# AS3364_bus_mixer_v2_1.net
KiCad netlist of a schematic drawn in EAGLE
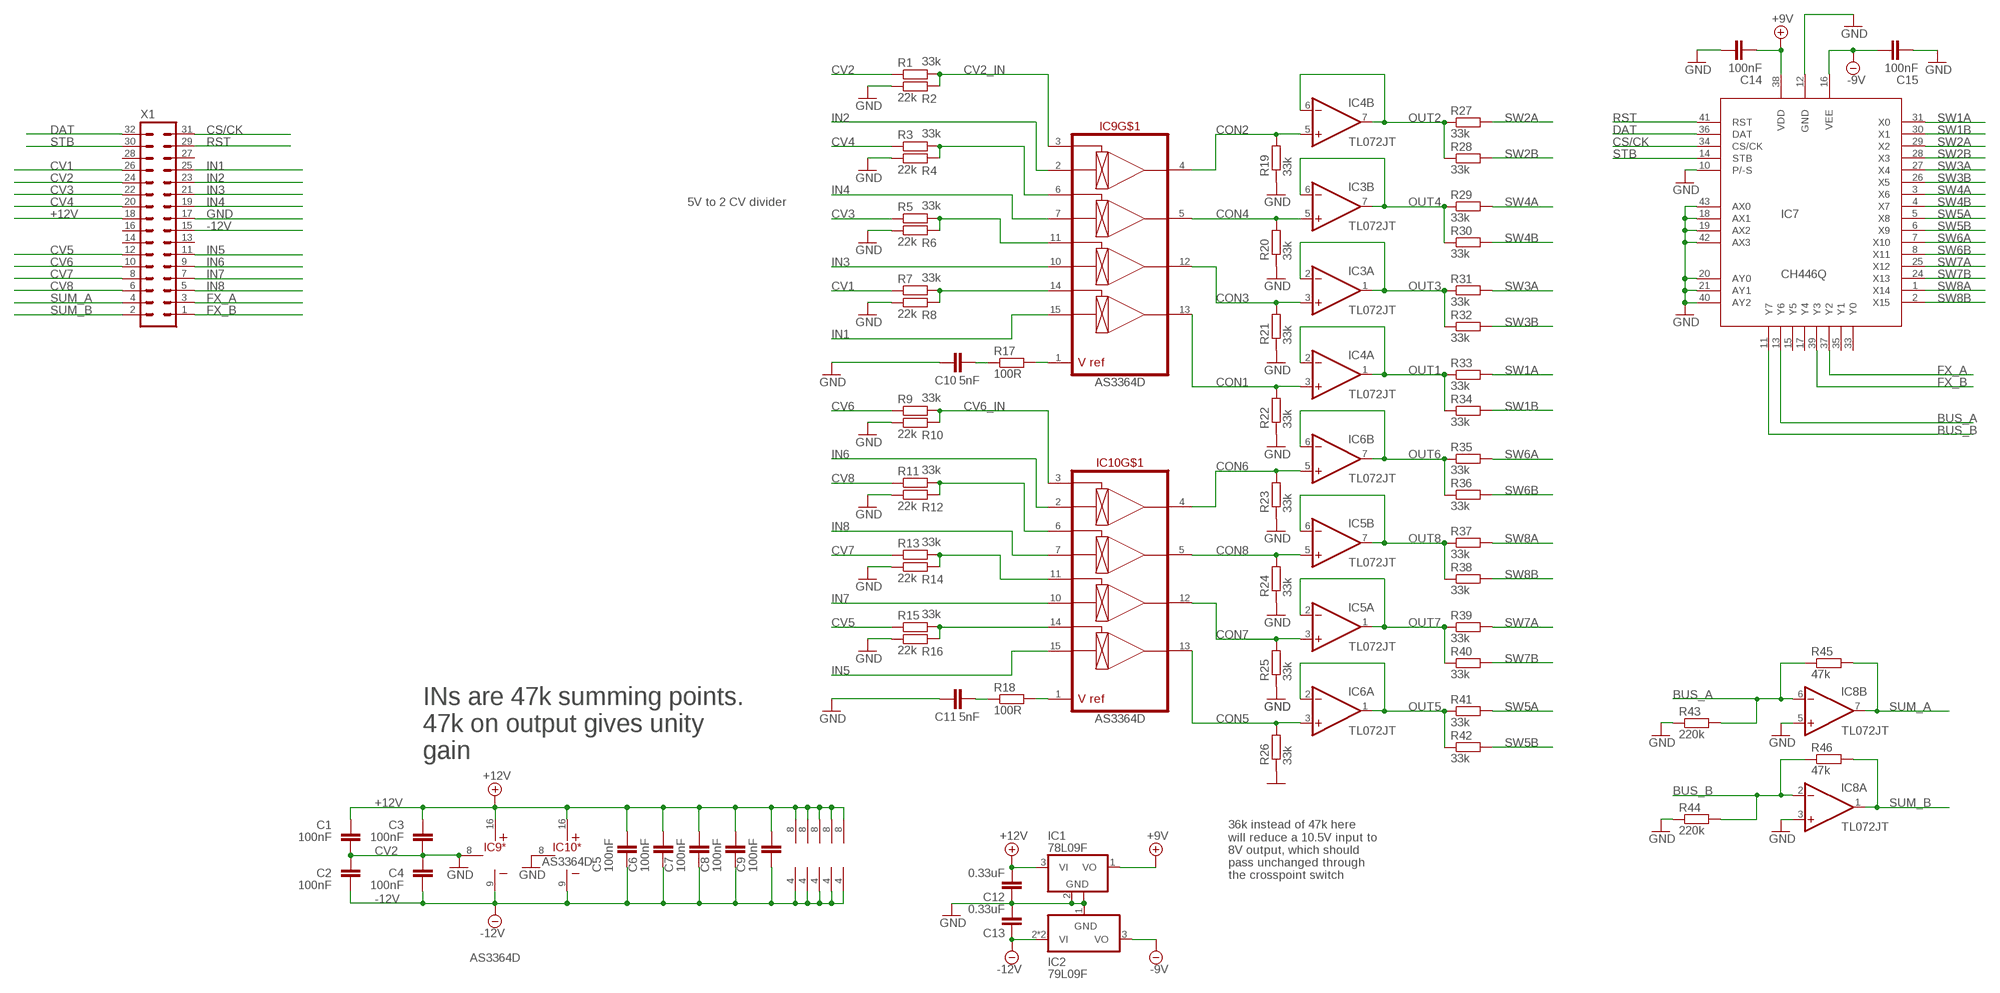
[diagram p0: schematic, sheet 1]

(export (version "E")
  (design (tool "Eeschema 10.0.6"))
  (components
    (comp (ref "C1")
      (value "100nF")
      (footprint "eagle-import:C0402")
      (libsource (lib "eagle-import") (part "C-EUC0402"))
    )
    (comp (ref "C2")
      (value "100nF")
      (footprint "eagle-import:C0402")
      (libsource (lib "eagle-import") (part "C-EUC0402"))
    )
    (comp (ref "C3")
      (value "100nF")
      (footprint "eagle-import:C0402")
      (libsource (lib "eagle-import") (part "C-EUC0402"))
    )
    (comp (ref "C4")
      (value "100nF")
      (footprint "eagle-import:C0402")
      (libsource (lib "eagle-import") (part "C-EUC0402"))
    )
    (comp (ref "C5")
      (value "100nF")
      (footprint "eagle-import:C0402")
      (libsource (lib "eagle-import") (part "C-EUC0402"))
    )
    (comp (ref "C6")
      (value "100nF")
      (footprint "eagle-import:C0402")
      (libsource (lib "eagle-import") (part "C-EUC0402"))
    )
    (comp (ref "C7")
      (value "100nF")
      (footprint "eagle-import:C0402")
      (libsource (lib "eagle-import") (part "C-EUC0402"))
    )
    (comp (ref "C8")
      (value "100nF")
      (footprint "eagle-import:C0402")
      (libsource (lib "eagle-import") (part "C-EUC0402"))
    )
    (comp (ref "C9")
      (value "100nF")
      (footprint "eagle-import:C0402")
      (libsource (lib "eagle-import") (part "C-EUC0402"))
    )
    (comp (ref "C10")
      (value "5nF")
      (footprint "eagle-import:C0402")
      (libsource (lib "eagle-import") (part "C-EUC0402"))
    )
    (comp (ref "C11")
      (value "5nF")
      (footprint "eagle-import:C0402")
      (libsource (lib "eagle-import") (part "C-EUC0402"))
    )
    (comp (ref "C12")
      (value "0.33uF")
      (footprint "eagle-import:C0603")
      (libsource (lib "eagle-import") (part "resistor_C-EUC0603"))
    )
    (comp (ref "C13")
      (value "0.33uF")
      (footprint "eagle-import:C0603")
      (libsource (lib "eagle-import") (part "resistor_C-EUC0603"))
    )
    (comp (ref "C14")
      (value "100nF")
      (footprint "eagle-import:C0402")
      (libsource (lib "eagle-import") (part "C-EUC0402"))
    )
    (comp (ref "C15")
      (value "100nF")
      (footprint "eagle-import:C0402")
      (libsource (lib "eagle-import") (part "C-EUC0402"))
    )
    (comp (ref "IC1")
      (value "78L09F")
      (footprint "eagle-import:SOT89")
      (libsource (lib "eagle-import") (part "78LF09"))
    )
    (comp (ref "IC2")
      (value "79L09F")
      (footprint "eagle-import:SOT89")
      (libsource (lib "eagle-import") (part "79LF09"))
    )
    (comp (ref "IC3")
      (value "TL072JT")
      (footprint "eagle-import:TSSOP8J")
      (libsource (lib "eagle-import") (part "TL072JT"))
    )
    (comp (ref "IC4")
      (value "TL072JT")
      (footprint "eagle-import:TSSOP8J")
      (libsource (lib "eagle-import") (part "TL072JT"))
    )
    (comp (ref "IC5")
      (value "TL072JT")
      (footprint "eagle-import:TSSOP8J")
      (libsource (lib "eagle-import") (part "TL072JT"))
    )
    (comp (ref "IC6")
      (value "TL072JT")
      (footprint "eagle-import:TSSOP8J")
      (libsource (lib "eagle-import") (part "TL072JT"))
    )
    (comp (ref "IC7")
      (value "CH446Q")
      (footprint "eagle-import:LQFP-44-J")
      (libsource (lib "eagle-import") (part "CH446Q"))
    )
    (comp (ref "IC8")
      (value "TL072JT")
      (footprint "eagle-import:TSSOP8J")
      (libsource (lib "eagle-import") (part "TL072JT"))
    )
    (comp (ref "IC9")
      (value "AS3364D")
      (footprint "eagle-import:DIL16J")
      (libsource (lib "eagle-import") (part "AS3364D"))
    )
    (comp (ref "IC10")
      (value "AS3364D")
      (footprint "eagle-import:DIL16J")
      (libsource (lib "eagle-import") (part "AS3364D"))
    )
    (comp (ref "R1")
      (value "33k")
      (footprint "eagle-import:R0402")
      (libsource (lib "eagle-import") (part "R-EU_R0402"))
    )
    (comp (ref "R2")
      (value "22k")
      (footprint "eagle-import:R0402")
      (libsource (lib "eagle-import") (part "R-EU_R0402"))
    )
    (comp (ref "R3")
      (value "33k")
      (footprint "eagle-import:R0402")
      (libsource (lib "eagle-import") (part "R-EU_R0402"))
    )
    (comp (ref "R4")
      (value "22k")
      (footprint "eagle-import:R0402")
      (libsource (lib "eagle-import") (part "R-EU_R0402"))
    )
    (comp (ref "R5")
      (value "33k")
      (footprint "eagle-import:R0402")
      (libsource (lib "eagle-import") (part "R-EU_R0402"))
    )
    (comp (ref "R6")
      (value "22k")
      (footprint "eagle-import:R0402")
      (libsource (lib "eagle-import") (part "R-EU_R0402"))
    )
    (comp (ref "R7")
      (value "33k")
      (footprint "eagle-import:R0402")
      (libsource (lib "eagle-import") (part "R-EU_R0402"))
    )
    (comp (ref "R8")
      (value "22k")
      (footprint "eagle-import:R0402")
      (libsource (lib "eagle-import") (part "R-EU_R0402"))
    )
    (comp (ref "R9")
      (value "33k")
      (footprint "eagle-import:R0402")
      (libsource (lib "eagle-import") (part "R-EU_R0402"))
    )
    (comp (ref "R10")
      (value "22k")
      (footprint "eagle-import:R0402")
      (libsource (lib "eagle-import") (part "R-EU_R0402"))
    )
    (comp (ref "R11")
      (value "33k")
      (footprint "eagle-import:R0402")
      (libsource (lib "eagle-import") (part "R-EU_R0402"))
    )
    (comp (ref "R12")
      (value "22k")
      (footprint "eagle-import:R0402")
      (libsource (lib "eagle-import") (part "R-EU_R0402"))
    )
    (comp (ref "R13")
      (value "33k")
      (footprint "eagle-import:R0402")
      (libsource (lib "eagle-import") (part "R-EU_R0402"))
    )
    (comp (ref "R14")
      (value "22k")
      (footprint "eagle-import:R0402")
      (libsource (lib "eagle-import") (part "R-EU_R0402"))
    )
    (comp (ref "R15")
      (value "33k")
      (footprint "eagle-import:R0402")
      (libsource (lib "eagle-import") (part "R-EU_R0402"))
    )
    (comp (ref "R16")
      (value "22k")
      (footprint "eagle-import:R0402")
      (libsource (lib "eagle-import") (part "R-EU_R0402"))
    )
    (comp (ref "R17")
      (value "100R")
      (footprint "eagle-import:R0402")
      (libsource (lib "eagle-import") (part "R-EU_R0402"))
    )
    (comp (ref "R18")
      (value "100R")
      (footprint "eagle-import:R0402")
      (libsource (lib "eagle-import") (part "R-EU_R0402"))
    )
    (comp (ref "R19")
      (value "33k")
      (footprint "eagle-import:R0402")
      (libsource (lib "eagle-import") (part "R-EU_R0402"))
    )
    (comp (ref "R20")
      (value "33k")
      (footprint "eagle-import:R0402")
      (libsource (lib "eagle-import") (part "R-EU_R0402"))
    )
    (comp (ref "R21")
      (value "33k")
      (footprint "eagle-import:R0402")
      (libsource (lib "eagle-import") (part "R-EU_R0402"))
    )
    (comp (ref "R22")
      (value "33k")
      (footprint "eagle-import:R0402")
      (libsource (lib "eagle-import") (part "R-EU_R0402"))
    )
    (comp (ref "R23")
      (value "33k")
      (footprint "eagle-import:R0402")
      (libsource (lib "eagle-import") (part "R-EU_R0402"))
    )
    (comp (ref "R24")
      (value "33k")
      (footprint "eagle-import:R0402")
      (libsource (lib "eagle-import") (part "R-EU_R0402"))
    )
    (comp (ref "R25")
      (value "33k")
      (footprint "eagle-import:R0402")
      (libsource (lib "eagle-import") (part "R-EU_R0402"))
    )
    (comp (ref "R26")
      (value "33k")
      (footprint "eagle-import:R0402")
      (libsource (lib "eagle-import") (part "R-EU_R0402"))
    )
    (comp (ref "R27")
      (value "33k")
      (footprint "eagle-import:R0402")
      (libsource (lib "eagle-import") (part "R-EU_R0402"))
    )
    (comp (ref "R28")
      (value "33k")
      (footprint "eagle-import:R0402")
      (libsource (lib "eagle-import") (part "R-EU_R0402"))
    )
    (comp (ref "R29")
      (value "33k")
      (footprint "eagle-import:R0402")
      (libsource (lib "eagle-import") (part "R-EU_R0402"))
    )
    (comp (ref "R30")
      (value "33k")
      (footprint "eagle-import:R0402")
      (libsource (lib "eagle-import") (part "R-EU_R0402"))
    )
    (comp (ref "R31")
      (value "33k")
      (footprint "eagle-import:R0402")
      (libsource (lib "eagle-import") (part "R-EU_R0402"))
    )
    (comp (ref "R32")
      (value "33k")
      (footprint "eagle-import:R0402")
      (libsource (lib "eagle-import") (part "R-EU_R0402"))
    )
    (comp (ref "R33")
      (value "33k")
      (footprint "eagle-import:R0402")
      (libsource (lib "eagle-import") (part "R-EU_R0402"))
    )
    (comp (ref "R34")
      (value "33k")
      (footprint "eagle-import:R0402")
      (libsource (lib "eagle-import") (part "R-EU_R0402"))
    )
    (comp (ref "R35")
      (value "33k")
      (footprint "eagle-import:R0402")
      (libsource (lib "eagle-import") (part "R-EU_R0402"))
    )
    (comp (ref "R36")
      (value "33k")
      (footprint "eagle-import:R0402")
      (libsource (lib "eagle-import") (part "R-EU_R0402"))
    )
    (comp (ref "R37")
      (value "33k")
      (footprint "eagle-import:R0402")
      (libsource (lib "eagle-import") (part "R-EU_R0402"))
    )
    (comp (ref "R38")
      (value "33k")
      (footprint "eagle-import:R0402")
      (libsource (lib "eagle-import") (part "R-EU_R0402"))
    )
    (comp (ref "R39")
      (value "33k")
      (footprint "eagle-import:R0402")
      (libsource (lib "eagle-import") (part "R-EU_R0402"))
    )
    (comp (ref "R40")
      (value "33k")
      (footprint "eagle-import:R0402")
      (libsource (lib "eagle-import") (part "R-EU_R0402"))
    )
    (comp (ref "R41")
      (value "33k")
      (footprint "eagle-import:R0402")
      (libsource (lib "eagle-import") (part "R-EU_R0402"))
    )
    (comp (ref "R42")
      (value "33k")
      (footprint "eagle-import:R0402")
      (libsource (lib "eagle-import") (part "R-EU_R0402"))
    )
    (comp (ref "R43")
      (value "220k")
      (footprint "eagle-import:R0402")
      (libsource (lib "eagle-import") (part "R-EU_R0402"))
    )
    (comp (ref "R44")
      (value "220k")
      (footprint "eagle-import:R0402")
      (libsource (lib "eagle-import") (part "R-EU_R0402"))
    )
    (comp (ref "R45")
      (value "47k")
      (footprint "eagle-import:R0402")
      (libsource (lib "eagle-import") (part "R-EU_R0402"))
    )
    (comp (ref "R46")
      (value "47k")
      (footprint "eagle-import:R0402")
      (libsource (lib "eagle-import") (part "R-EU_R0402"))
    )
    (comp (ref "X1")
      (value "MA16-2WJ")
      (footprint "eagle-import:MA16-2WJ")
      (libsource (lib "eagle-import") (part "MA16-2WJ"))
    )
  )
  (nets
    (net (code "1") (name "+9V") (class "Default")
      (node (ref "C14") (pin "1") (pinfunction "1_1") (pintype "passive"))
      (node (ref "IC1") (pin "1") (pinfunction "VO_1") (pintype "passive"))
      (node (ref "IC7") (pin "38") (pinfunction "VDD_38") (pintype "power_in"))
    )
    (net (code "2") (name "+12V") (class "Default")
      (node (ref "C1") (pin "2") (pinfunction "2_2") (pintype "passive"))
      (node (ref "C12") (pin "2") (pinfunction "2_2") (pintype "passive"))
      (node (ref "C3") (pin "2") (pinfunction "2_2") (pintype "passive"))
      (node (ref "C5") (pin "2") (pinfunction "2_2") (pintype "passive"))
      (node (ref "C6") (pin "2") (pinfunction "2_2") (pintype "passive"))
      (node (ref "C7") (pin "2") (pinfunction "2_2") (pintype "passive"))
      (node (ref "C8") (pin "2") (pinfunction "2_2") (pintype "passive"))
      (node (ref "C9") (pin "2") (pinfunction "2_2") (pintype "passive"))
      (node (ref "IC1") (pin "3") (pinfunction "VI_3") (pintype "input"))
      (node (ref "IC10") (pin "16") (pinfunction "V+_16") (pintype "power_in"))
      (node (ref "IC3") (pin "8") (pinfunction "V+_8") (pintype "power_in"))
      (node (ref "IC4") (pin "8") (pinfunction "V+_8") (pintype "power_in"))
      (node (ref "IC5") (pin "8") (pinfunction "V+_8") (pintype "power_in"))
      (node (ref "IC6") (pin "8") (pinfunction "V+_8") (pintype "power_in"))
      (node (ref "IC8") (pin "8") (pinfunction "V+_8") (pintype "power_in"))
      (node (ref "IC9") (pin "16") (pinfunction "V+_16") (pintype "power_in"))
      (node (ref "X1") (pin "18") (pinfunction "18_18") (pintype "passive"))
    )
    (net (code "3") (name "-9V") (class "Default")
      (node (ref "C15") (pin "2") (pinfunction "2_2") (pintype "passive"))
      (node (ref "IC2") (pin "3") (pinfunction "VO_3") (pintype "passive"))
      (node (ref "IC7") (pin "16") (pinfunction "VEE_16") (pintype "power_in"))
    )
    (net (code "4") (name "-12V") (class "Default")
      (node (ref "C13") (pin "1") (pinfunction "1_1") (pintype "passive"))
      (node (ref "C2") (pin "1") (pinfunction "1_1") (pintype "passive"))
      (node (ref "C4") (pin "1") (pinfunction "1_1") (pintype "passive"))
      (node (ref "C5") (pin "1") (pinfunction "1_1") (pintype "passive"))
      (node (ref "C6") (pin "1") (pinfunction "1_1") (pintype "passive"))
      (node (ref "C7") (pin "1") (pinfunction "1_1") (pintype "passive"))
      (node (ref "C8") (pin "1") (pinfunction "1_1") (pintype "passive"))
      (node (ref "C9") (pin "1") (pinfunction "1_1") (pintype "passive"))
      (node (ref "IC10") (pin "9") (pinfunction "V-_9") (pintype "power_in"))
      (node (ref "IC2") (pin "2") (pinfunction "VI_2") (pintype "input"))
      (node (ref "IC2") (pin "2@1") (pinfunction "VI_2@1") (pintype "input"))
      (node (ref "IC3") (pin "4") (pinfunction "V-_4") (pintype "power_in"))
      (node (ref "IC4") (pin "4") (pinfunction "V-_4") (pintype "power_in"))
      (node (ref "IC5") (pin "4") (pinfunction "V-_4") (pintype "power_in"))
      (node (ref "IC6") (pin "4") (pinfunction "V-_4") (pintype "power_in"))
      (node (ref "IC8") (pin "4") (pinfunction "V-_4") (pintype "power_in"))
      (node (ref "IC9") (pin "9") (pinfunction "V-_9") (pintype "power_in"))
      (node (ref "X1") (pin "15") (pinfunction "15_15") (pintype "passive"))
    )
    (net (code "5") (name "/BUS_A") (class "Default")
      (node (ref "IC7") (pin "13") (pinfunction "Y6_13") (pintype "bidirectional"))
      (node (ref "IC8") (pin "6") (pinfunction "-IN_6") (pintype "input"))
      (node (ref "R43") (pin "2") (pinfunction "2_2") (pintype "passive"))
      (node (ref "R45") (pin "1") (pinfunction "1_1") (pintype "passive"))
    )
    (net (code "6") (name "/BUS_B") (class "Default")
      (node (ref "IC7") (pin "11") (pinfunction "Y7_11") (pintype "bidirectional"))
      (node (ref "IC8") (pin "2") (pinfunction "-IN_2") (pintype "input"))
      (node (ref "R44") (pin "2") (pinfunction "2_2") (pintype "passive"))
      (node (ref "R46") (pin "1") (pinfunction "1_1") (pintype "passive"))
    )
    (net (code "7") (name "/CON1") (class "Default")
      (node (ref "IC4") (pin "3") (pinfunction "+IN_3") (pintype "input"))
      (node (ref "IC9") (pin "13") (pinfunction "OUT4_13") (pintype "output"))
      (node (ref "R22") (pin "2") (pinfunction "2_2") (pintype "passive"))
    )
    (net (code "8") (name "/CON2") (class "Default")
      (node (ref "IC4") (pin "5") (pinfunction "+IN_5") (pintype "input"))
      (node (ref "IC9") (pin "4") (pinfunction "OUT1_4") (pintype "output"))
      (node (ref "R19") (pin "2") (pinfunction "2_2") (pintype "passive"))
    )
    (net (code "9") (name "/CON3") (class "Default")
      (node (ref "IC3") (pin "3") (pinfunction "+IN_3") (pintype "input"))
      (node (ref "IC9") (pin "12") (pinfunction "OUT3_12") (pintype "output"))
      (node (ref "R21") (pin "2") (pinfunction "2_2") (pintype "passive"))
    )
    (net (code "10") (name "/CON4") (class "Default")
      (node (ref "IC3") (pin "5") (pinfunction "+IN_5") (pintype "input"))
      (node (ref "IC9") (pin "5") (pinfunction "OUT2_5") (pintype "output"))
      (node (ref "R20") (pin "2") (pinfunction "2_2") (pintype "passive"))
    )
    (net (code "11") (name "/CON5") (class "Default")
      (node (ref "IC10") (pin "13") (pinfunction "OUT4_13") (pintype "output"))
      (node (ref "IC6") (pin "3") (pinfunction "+IN_3") (pintype "input"))
      (node (ref "R26") (pin "2") (pinfunction "2_2") (pintype "passive"))
    )
    (net (code "12") (name "/CON6") (class "Default")
      (node (ref "IC10") (pin "4") (pinfunction "OUT1_4") (pintype "output"))
      (node (ref "IC6") (pin "5") (pinfunction "+IN_5") (pintype "input"))
      (node (ref "R23") (pin "2") (pinfunction "2_2") (pintype "passive"))
    )
    (net (code "13") (name "/CON7") (class "Default")
      (node (ref "IC10") (pin "12") (pinfunction "OUT3_12") (pintype "output"))
      (node (ref "IC5") (pin "3") (pinfunction "+IN_3") (pintype "input"))
      (node (ref "R25") (pin "2") (pinfunction "2_2") (pintype "passive"))
    )
    (net (code "14") (name "/CON8") (class "Default")
      (node (ref "IC10") (pin "5") (pinfunction "OUT2_5") (pintype "output"))
      (node (ref "IC5") (pin "5") (pinfunction "+IN_5") (pintype "input"))
      (node (ref "R24") (pin "2") (pinfunction "2_2") (pintype "passive"))
    )
    (net (code "15") (name "/CS{slash}CK") (class "Default")
      (node (ref "IC7") (pin "34") (pinfunction "CS/CK_34") (pintype "bidirectional"))
      (node (ref "X1") (pin "31") (pinfunction "31_31") (pintype "passive"))
    )
    (net (code "16") (name "/CV1") (class "Default")
      (node (ref "R7") (pin "1") (pinfunction "1_1") (pintype "passive"))
      (node (ref "X1") (pin "26") (pinfunction "26_26") (pintype "passive"))
    )
    (net (code "17") (name "/CV2") (class "Default")
      (node (ref "R1") (pin "1") (pinfunction "1_1") (pintype "passive"))
      (node (ref "X1") (pin "24") (pinfunction "24_24") (pintype "passive"))
    )
    (net (code "18") (name "/CV2_IN") (class "Default")
      (node (ref "IC9") (pin "3") (pinfunction "CV1_3") (pintype "input"))
      (node (ref "R1") (pin "2") (pinfunction "2_2") (pintype "passive"))
      (node (ref "R2") (pin "2") (pinfunction "2_2") (pintype "passive"))
    )
    (net (code "19") (name "/CV3") (class "Default")
      (node (ref "R5") (pin "1") (pinfunction "1_1") (pintype "passive"))
      (node (ref "X1") (pin "22") (pinfunction "22_22") (pintype "passive"))
    )
    (net (code "20") (name "/CV4") (class "Default")
      (node (ref "R3") (pin "1") (pinfunction "1_1") (pintype "passive"))
      (node (ref "X1") (pin "20") (pinfunction "20_20") (pintype "passive"))
    )
    (net (code "21") (name "/CV5") (class "Default")
      (node (ref "R15") (pin "1") (pinfunction "1_1") (pintype "passive"))
      (node (ref "X1") (pin "12") (pinfunction "12_12") (pintype "passive"))
    )
    (net (code "22") (name "/CV6") (class "Default")
      (node (ref "R9") (pin "1") (pinfunction "1_1") (pintype "passive"))
      (node (ref "X1") (pin "10") (pinfunction "10_10") (pintype "passive"))
    )
    (net (code "23") (name "/CV6_IN") (class "Default")
      (node (ref "IC10") (pin "3") (pinfunction "CV1_3") (pintype "input"))
      (node (ref "R10") (pin "2") (pinfunction "2_2") (pintype "passive"))
      (node (ref "R9") (pin "2") (pinfunction "2_2") (pintype "passive"))
    )
    (net (code "24") (name "/CV7") (class "Default")
      (node (ref "R13") (pin "1") (pinfunction "1_1") (pintype "passive"))
      (node (ref "X1") (pin "8") (pinfunction "8_8") (pintype "passive"))
    )
    (net (code "25") (name "/CV8") (class "Default")
      (node (ref "R11") (pin "1") (pinfunction "1_1") (pintype "passive"))
      (node (ref "X1") (pin "6") (pinfunction "6_6") (pintype "passive"))
    )
    (net (code "26") (name "/DAT") (class "Default")
      (node (ref "IC7") (pin "36") (pinfunction "DAT_36") (pintype "bidirectional"))
      (node (ref "X1") (pin "32") (pinfunction "32_32") (pintype "passive"))
    )
    (net (code "27") (name "/FX_A") (class "Default")
      (node (ref "IC7") (pin "37") (pinfunction "Y2_37") (pintype "bidirectional"))
      (node (ref "X1") (pin "3") (pinfunction "3_3") (pintype "passive"))
    )
    (net (code "28") (name "/FX_B") (class "Default")
      (node (ref "IC7") (pin "39") (pinfunction "Y3_39") (pintype "bidirectional"))
      (node (ref "X1") (pin "1") (pinfunction "1_1") (pintype "passive"))
    )
    (net (code "29") (name "/IN1") (class "Default")
      (node (ref "IC9") (pin "15") (pinfunction "IN4_15") (pintype "input"))
      (node (ref "X1") (pin "25") (pinfunction "25_25") (pintype "passive"))
    )
    (net (code "30") (name "/IN2") (class "Default")
      (node (ref "IC9") (pin "2") (pinfunction "IN1_2") (pintype "input"))
      (node (ref "X1") (pin "23") (pinfunction "23_23") (pintype "passive"))
    )
    (net (code "31") (name "/IN3") (class "Default")
      (node (ref "IC9") (pin "10") (pinfunction "IN3_10") (pintype "input"))
      (node (ref "X1") (pin "21") (pinfunction "21_21") (pintype "passive"))
    )
    (net (code "32") (name "/IN4") (class "Default")
      (node (ref "IC9") (pin "7") (pinfunction "IN2_7") (pintype "input"))
      (node (ref "X1") (pin "19") (pinfunction "19_19") (pintype "passive"))
    )
    (net (code "33") (name "/IN5") (class "Default")
      (node (ref "IC10") (pin "15") (pinfunction "IN4_15") (pintype "input"))
      (node (ref "X1") (pin "11") (pinfunction "11_11") (pintype "passive"))
    )
    (net (code "34") (name "/IN6") (class "Default")
      (node (ref "IC10") (pin "2") (pinfunction "IN1_2") (pintype "input"))
      (node (ref "X1") (pin "9") (pinfunction "9_9") (pintype "passive"))
    )
    (net (code "35") (name "/IN7") (class "Default")
      (node (ref "IC10") (pin "10") (pinfunction "IN3_10") (pintype "input"))
      (node (ref "X1") (pin "7") (pinfunction "7_7") (pintype "passive"))
    )
    (net (code "36") (name "/IN8") (class "Default")
      (node (ref "IC10") (pin "7") (pinfunction "IN2_7") (pintype "input"))
      (node (ref "X1") (pin "5") (pinfunction "5_5") (pintype "passive"))
    )
    (net (code "37") (name "/OUT1") (class "Default")
      (node (ref "IC4") (pin "1") (pinfunction "OUT_1") (pintype "output"))
      (node (ref "IC4") (pin "2") (pinfunction "-IN_2") (pintype "input"))
      (node (ref "R33") (pin "1") (pinfunction "1_1") (pintype "passive"))
      (node (ref "R34") (pin "1") (pinfunction "1_1") (pintype "passive"))
    )
    (net (code "38") (name "/OUT2") (class "Default")
      (node (ref "IC4") (pin "6") (pinfunction "-IN_6") (pintype "input"))
      (node (ref "IC4") (pin "7") (pinfunction "OUT_7") (pintype "output"))
      (node (ref "R27") (pin "1") (pinfunction "1_1") (pintype "passive"))
      (node (ref "R28") (pin "1") (pinfunction "1_1") (pintype "passive"))
    )
    (net (code "39") (name "/OUT3") (class "Default")
      (node (ref "IC3") (pin "1") (pinfunction "OUT_1") (pintype "output"))
      (node (ref "IC3") (pin "2") (pinfunction "-IN_2") (pintype "input"))
      (node (ref "R31") (pin "1") (pinfunction "1_1") (pintype "passive"))
      (node (ref "R32") (pin "1") (pinfunction "1_1") (pintype "passive"))
    )
    (net (code "40") (name "/OUT4") (class "Default")
      (node (ref "IC3") (pin "6") (pinfunction "-IN_6") (pintype "input"))
      (node (ref "IC3") (pin "7") (pinfunction "OUT_7") (pintype "output"))
      (node (ref "R29") (pin "1") (pinfunction "1_1") (pintype "passive"))
      (node (ref "R30") (pin "1") (pinfunction "1_1") (pintype "passive"))
    )
    (net (code "41") (name "/OUT5") (class "Default")
      (node (ref "IC6") (pin "1") (pinfunction "OUT_1") (pintype "output"))
      (node (ref "IC6") (pin "2") (pinfunction "-IN_2") (pintype "input"))
      (node (ref "R41") (pin "1") (pinfunction "1_1") (pintype "passive"))
      (node (ref "R42") (pin "1") (pinfunction "1_1") (pintype "passive"))
    )
    (net (code "42") (name "/OUT6") (class "Default")
      (node (ref "IC6") (pin "6") (pinfunction "-IN_6") (pintype "input"))
      (node (ref "IC6") (pin "7") (pinfunction "OUT_7") (pintype "output"))
      (node (ref "R35") (pin "1") (pinfunction "1_1") (pintype "passive"))
      (node (ref "R36") (pin "1") (pinfunction "1_1") (pintype "passive"))
    )
    (net (code "43") (name "/OUT7") (class "Default")
      (node (ref "IC5") (pin "1") (pinfunction "OUT_1") (pintype "output"))
      (node (ref "IC5") (pin "2") (pinfunction "-IN_2") (pintype "input"))
      (node (ref "R39") (pin "1") (pinfunction "1_1") (pintype "passive"))
      (node (ref "R40") (pin "1") (pinfunction "1_1") (pintype "passive"))
    )
    (net (code "44") (name "/OUT8") (class "Default")
      (node (ref "IC5") (pin "6") (pinfunction "-IN_6") (pintype "input"))
      (node (ref "IC5") (pin "7") (pinfunction "OUT_7") (pintype "output"))
      (node (ref "R37") (pin "1") (pinfunction "1_1") (pintype "passive"))
      (node (ref "R38") (pin "1") (pinfunction "1_1") (pintype "passive"))
    )
    (net (code "45") (name "/RST") (class "Default")
      (node (ref "IC7") (pin "41") (pinfunction "RST_41") (pintype "bidirectional"))
      (node (ref "X1") (pin "29") (pinfunction "29_29") (pintype "passive"))
    )
    (net (code "46") (name "/STB") (class "Default")
      (node (ref "IC7") (pin "14") (pinfunction "STB_14") (pintype "bidirectional"))
      (node (ref "X1") (pin "30") (pinfunction "30_30") (pintype "passive"))
    )
    (net (code "47") (name "/SUM_A") (class "Default")
      (node (ref "IC8") (pin "7") (pinfunction "OUT_7") (pintype "output"))
      (node (ref "R45") (pin "2") (pinfunction "2_2") (pintype "passive"))
      (node (ref "X1") (pin "4") (pinfunction "4_4") (pintype "passive"))
    )
    (net (code "48") (name "/SUM_B") (class "Default")
      (node (ref "IC8") (pin "1") (pinfunction "OUT_1") (pintype "output"))
      (node (ref "R46") (pin "2") (pinfunction "2_2") (pintype "passive"))
      (node (ref "X1") (pin "2") (pinfunction "2_2") (pintype "passive"))
    )
    (net (code "49") (name "/SW1A") (class "Default")
      (node (ref "IC7") (pin "31") (pinfunction "X0_31") (pintype "bidirectional"))
      (node (ref "R33") (pin "2") (pinfunction "2_2") (pintype "passive"))
    )
    (net (code "50") (name "/SW1B") (class "Default")
      (node (ref "IC7") (pin "30") (pinfunction "X1_30") (pintype "bidirectional"))
      (node (ref "R34") (pin "2") (pinfunction "2_2") (pintype "passive"))
    )
    (net (code "51") (name "/SW2A") (class "Default")
      (node (ref "IC7") (pin "29") (pinfunction "X2_29") (pintype "bidirectional"))
      (node (ref "R27") (pin "2") (pinfunction "2_2") (pintype "passive"))
    )
    (net (code "52") (name "/SW2B") (class "Default")
      (node (ref "IC7") (pin "28") (pinfunction "X3_28") (pintype "bidirectional"))
      (node (ref "R28") (pin "2") (pinfunction "2_2") (pintype "passive"))
    )
    (net (code "53") (name "/SW3A") (class "Default")
      (node (ref "IC7") (pin "27") (pinfunction "X4_27") (pintype "bidirectional"))
      (node (ref "R31") (pin "2") (pinfunction "2_2") (pintype "passive"))
    )
    (net (code "54") (name "/SW3B") (class "Default")
      (node (ref "IC7") (pin "26") (pinfunction "X5_26") (pintype "bidirectional"))
      (node (ref "R32") (pin "2") (pinfunction "2_2") (pintype "passive"))
    )
    (net (code "55") (name "/SW4A") (class "Default")
      (node (ref "IC7") (pin "3") (pinfunction "X6_3") (pintype "bidirectional"))
      (node (ref "R29") (pin "2") (pinfunction "2_2") (pintype "passive"))
    )
    (net (code "56") (name "/SW4B") (class "Default")
      (node (ref "IC7") (pin "4") (pinfunction "X7_4") (pintype "bidirectional"))
      (node (ref "R30") (pin "2") (pinfunction "2_2") (pintype "passive"))
    )
    (net (code "57") (name "/SW5A") (class "Default")
      (node (ref "IC7") (pin "5") (pinfunction "X8_5") (pintype "bidirectional"))
      (node (ref "R41") (pin "2") (pinfunction "2_2") (pintype "passive"))
    )
    (net (code "58") (name "/SW5B") (class "Default")
      (node (ref "IC7") (pin "6") (pinfunction "X9_6") (pintype "bidirectional"))
      (node (ref "R42") (pin "2") (pinfunction "2_2") (pintype "passive"))
    )
    (net (code "59") (name "/SW6A") (class "Default")
      (node (ref "IC7") (pin "7") (pinfunction "X10_7") (pintype "bidirectional"))
      (node (ref "R35") (pin "2") (pinfunction "2_2") (pintype "passive"))
    )
    (net (code "60") (name "/SW6B") (class "Default")
      (node (ref "IC7") (pin "8") (pinfunction "X11_8") (pintype "bidirectional"))
      (node (ref "R36") (pin "2") (pinfunction "2_2") (pintype "passive"))
    )
    (net (code "61") (name "/SW7A") (class "Default")
      (node (ref "IC7") (pin "25") (pinfunction "X12_25") (pintype "bidirectional"))
      (node (ref "R39") (pin "2") (pinfunction "2_2") (pintype "passive"))
    )
    (net (code "62") (name "/SW7B") (class "Default")
      (node (ref "IC7") (pin "24") (pinfunction "X13_24") (pintype "bidirectional"))
      (node (ref "R40") (pin "2") (pinfunction "2_2") (pintype "passive"))
    )
    (net (code "63") (name "/SW8A") (class "Default")
      (node (ref "IC7") (pin "1") (pinfunction "X14_1") (pintype "bidirectional"))
      (node (ref "R37") (pin "2") (pinfunction "2_2") (pintype "passive"))
    )
    (net (code "64") (name "/SW8B") (class "Default")
      (node (ref "IC7") (pin "2") (pinfunction "X15_2") (pintype "bidirectional"))
      (node (ref "R38") (pin "2") (pinfunction "2_2") (pintype "passive"))
    )
    (net (code "65") (name "GND") (class "Default")
      (node (ref "C1") (pin "1") (pinfunction "1_1") (pintype "passive"))
      (node (ref "C10") (pin "1") (pinfunction "1_1") (pintype "passive"))
      (node (ref "C11") (pin "1") (pinfunction "1_1") (pintype "passive"))
      (node (ref "C12") (pin "1") (pinfunction "1_1") (pintype "passive"))
      (node (ref "C13") (pin "2") (pinfunction "2_2") (pintype "passive"))
      (node (ref "C14") (pin "2") (pinfunction "2_2") (pintype "passive"))
      (node (ref "C15") (pin "1") (pinfunction "1_1") (pintype "passive"))
      (node (ref "C2") (pin "2") (pinfunction "2_2") (pintype "passive"))
      (node (ref "C3") (pin "1") (pinfunction "1_1") (pintype "passive"))
      (node (ref "C4") (pin "2") (pinfunction "2_2") (pintype "passive"))
      (node (ref "IC1") (pin "2") (pinfunction "GND_2") (pintype "passive"))
      (node (ref "IC1") (pin "2@1") (pinfunction "GND_2@1") (pintype "passive"))
      (node (ref "IC10") (pin "8") (pinfunction "GND_8") (pintype "power_in"))
      (node (ref "IC2") (pin "1") (pinfunction "GND_1") (pintype "passive"))
      (node (ref "IC7") (pin "10") (pinfunction "P/-S_10") (pintype "bidirectional"))
      (node (ref "IC7") (pin "12") (pinfunction "GND_12") (pintype "power_in"))
      (node (ref "IC7") (pin "18") (pinfunction "AX1_18") (pintype "bidirectional"))
      (node (ref "IC7") (pin "19") (pinfunction "AX2_19") (pintype "bidirectional"))
      (node (ref "IC7") (pin "20") (pinfunction "AY0_20") (pintype "bidirectional"))
      (node (ref "IC7") (pin "21") (pinfunction "AY1_21") (pintype "bidirectional"))
      (node (ref "IC7") (pin "40") (pinfunction "AY2_40") (pintype "bidirectional"))
      (node (ref "IC7") (pin "42") (pinfunction "AX3_42") (pintype "bidirectional"))
      (node (ref "IC7") (pin "43") (pinfunction "AX0_43") (pintype "bidirectional"))
      (node (ref "IC8") (pin "3") (pinfunction "+IN_3") (pintype "input"))
      (node (ref "IC8") (pin "5") (pinfunction "+IN_5") (pintype "input"))
      (node (ref "IC9") (pin "8") (pinfunction "GND_8") (pintype "power_in"))
      (node (ref "R10") (pin "1") (pinfunction "1_1") (pintype "passive"))
      (node (ref "R12") (pin "1") (pinfunction "1_1") (pintype "passive"))
      (node (ref "R14") (pin "1") (pinfunction "1_1") (pintype "passive"))
      (node (ref "R16") (pin "1") (pinfunction "1_1") (pintype "passive"))
      (node (ref "R19") (pin "1") (pinfunction "1_1") (pintype "passive"))
      (node (ref "R2") (pin "1") (pinfunction "1_1") (pintype "passive"))
      (node (ref "R20") (pin "1") (pinfunction "1_1") (pintype "passive"))
      (node (ref "R21") (pin "1") (pinfunction "1_1") (pintype "passive"))
      (node (ref "R22") (pin "1") (pinfunction "1_1") (pintype "passive"))
      (node (ref "R23") (pin "1") (pinfunction "1_1") (pintype "passive"))
      (node (ref "R24") (pin "1") (pinfunction "1_1") (pintype "passive"))
      (node (ref "R25") (pin "1") (pinfunction "1_1") (pintype "passive"))
      (node (ref "R26") (pin "1") (pinfunction "1_1") (pintype "passive"))
      (node (ref "R4") (pin "1") (pinfunction "1_1") (pintype "passive"))
      (node (ref "R43") (pin "1") (pinfunction "1_1") (pintype "passive"))
      (node (ref "R44") (pin "1") (pinfunction "1_1") (pintype "passive"))
      (node (ref "R6") (pin "1") (pinfunction "1_1") (pintype "passive"))
      (node (ref "R8") (pin "1") (pinfunction "1_1") (pintype "passive"))
      (node (ref "X1") (pin "17") (pinfunction "17_17") (pintype "passive"))
    )
    (net (code "66") (name "Net-(C10-Pad2)") (class "Default")
      (node (ref "C10") (pin "2") (pinfunction "2_2") (pintype "passive"))
      (node (ref "R17") (pin "1") (pinfunction "1_1") (pintype "passive"))
    )
    (net (code "67") (name "Net-(C11-Pad2)") (class "Default")
      (node (ref "C11") (pin "2") (pinfunction "2_2") (pintype "passive"))
      (node (ref "R18") (pin "1") (pinfunction "1_1") (pintype "passive"))
    )
    (net (code "68") (name "Net-(IC9B-CV2)") (class "Default")
      (node (ref "IC9") (pin "6") (pinfunction "CV2_6") (pintype "input"))
      (node (ref "R3") (pin "2") (pinfunction "2_2") (pintype "passive"))
      (node (ref "R4") (pin "2") (pinfunction "2_2") (pintype "passive"))
    )
    (net (code "69") (name "Net-(IC9B-CV3)") (class "Default")
      (node (ref "IC9") (pin "11") (pinfunction "CV3_11") (pintype "input"))
      (node (ref "R5") (pin "2") (pinfunction "2_2") (pintype "passive"))
      (node (ref "R6") (pin "2") (pinfunction "2_2") (pintype "passive"))
    )
    (net (code "70") (name "Net-(IC9B-CV4)") (class "Default")
      (node (ref "IC9") (pin "14") (pinfunction "CV4_14") (pintype "input"))
      (node (ref "R7") (pin "2") (pinfunction "2_2") (pintype "passive"))
      (node (ref "R8") (pin "2") (pinfunction "2_2") (pintype "passive"))
    )
    (net (code "71") (name "Net-(IC9B-VREF)") (class "Default")
      (node (ref "IC9") (pin "1") (pinfunction "VREF_1") (pintype "output"))
      (node (ref "R17") (pin "2") (pinfunction "2_2") (pintype "passive"))
    )
    (net (code "72") (name "Net-(IC10B-CV2)") (class "Default")
      (node (ref "IC10") (pin "6") (pinfunction "CV2_6") (pintype "input"))
      (node (ref "R11") (pin "2") (pinfunction "2_2") (pintype "passive"))
      (node (ref "R12") (pin "2") (pinfunction "2_2") (pintype "passive"))
    )
    (net (code "73") (name "Net-(IC10B-CV3)") (class "Default")
      (node (ref "IC10") (pin "11") (pinfunction "CV3_11") (pintype "input"))
      (node (ref "R13") (pin "2") (pinfunction "2_2") (pintype "passive"))
      (node (ref "R14") (pin "2") (pinfunction "2_2") (pintype "passive"))
    )
    (net (code "74") (name "Net-(IC10B-CV4)") (class "Default")
      (node (ref "IC10") (pin "14") (pinfunction "CV4_14") (pintype "input"))
      (node (ref "R15") (pin "2") (pinfunction "2_2") (pintype "passive"))
      (node (ref "R16") (pin "2") (pinfunction "2_2") (pintype "passive"))
    )
    (net (code "75") (name "Net-(IC10B-VREF)") (class "Default")
      (node (ref "IC10") (pin "1") (pinfunction "VREF_1") (pintype "output"))
      (node (ref "R18") (pin "2") (pinfunction "2_2") (pintype "passive"))
    )
    (net (code "76") (name "unconnected-(IC7-Y0-Pad33)") (class "Default")
      (node (ref "IC7") (pin "33") (pinfunction "Y0_33") (pintype "bidirectional"))
    )
    (net (code "77") (name "unconnected-(IC7-Y1-Pad35)") (class "Default")
      (node (ref "IC7") (pin "35") (pinfunction "Y1_35") (pintype "bidirectional"))
    )
    (net (code "78") (name "unconnected-(IC7-Y4-Pad17)") (class "Default")
      (node (ref "IC7") (pin "17") (pinfunction "Y4_17") (pintype "bidirectional"))
    )
    (net (code "79") (name "unconnected-(IC7-Y5-Pad15)") (class "Default")
      (node (ref "IC7") (pin "15") (pinfunction "Y5_15") (pintype "bidirectional"))
    )
    (net (code "80") (name "unconnected-(X1-Pad13)") (class "Default")
      (node (ref "X1") (pin "13") (pinfunction "13_13") (pintype "passive"))
    )
    (net (code "81") (name "unconnected-(X1-Pad14)") (class "Default")
      (node (ref "X1") (pin "14") (pinfunction "14_14") (pintype "passive"))
    )
    (net (code "82") (name "unconnected-(X1-Pad16)") (class "Default")
      (node (ref "X1") (pin "16") (pinfunction "16_16") (pintype "passive"))
    )
    (net (code "83") (name "unconnected-(X1-Pad27)") (class "Default")
      (node (ref "X1") (pin "27") (pinfunction "27_27") (pintype "passive"))
    )
    (net (code "84") (name "unconnected-(X1-Pad28)") (class "Default")
      (node (ref "X1") (pin "28") (pinfunction "28_28") (pintype "passive"))
    )
  )
)
